# integrated_adc.net
KiCad netlist of a schematic drawn in EAGLE
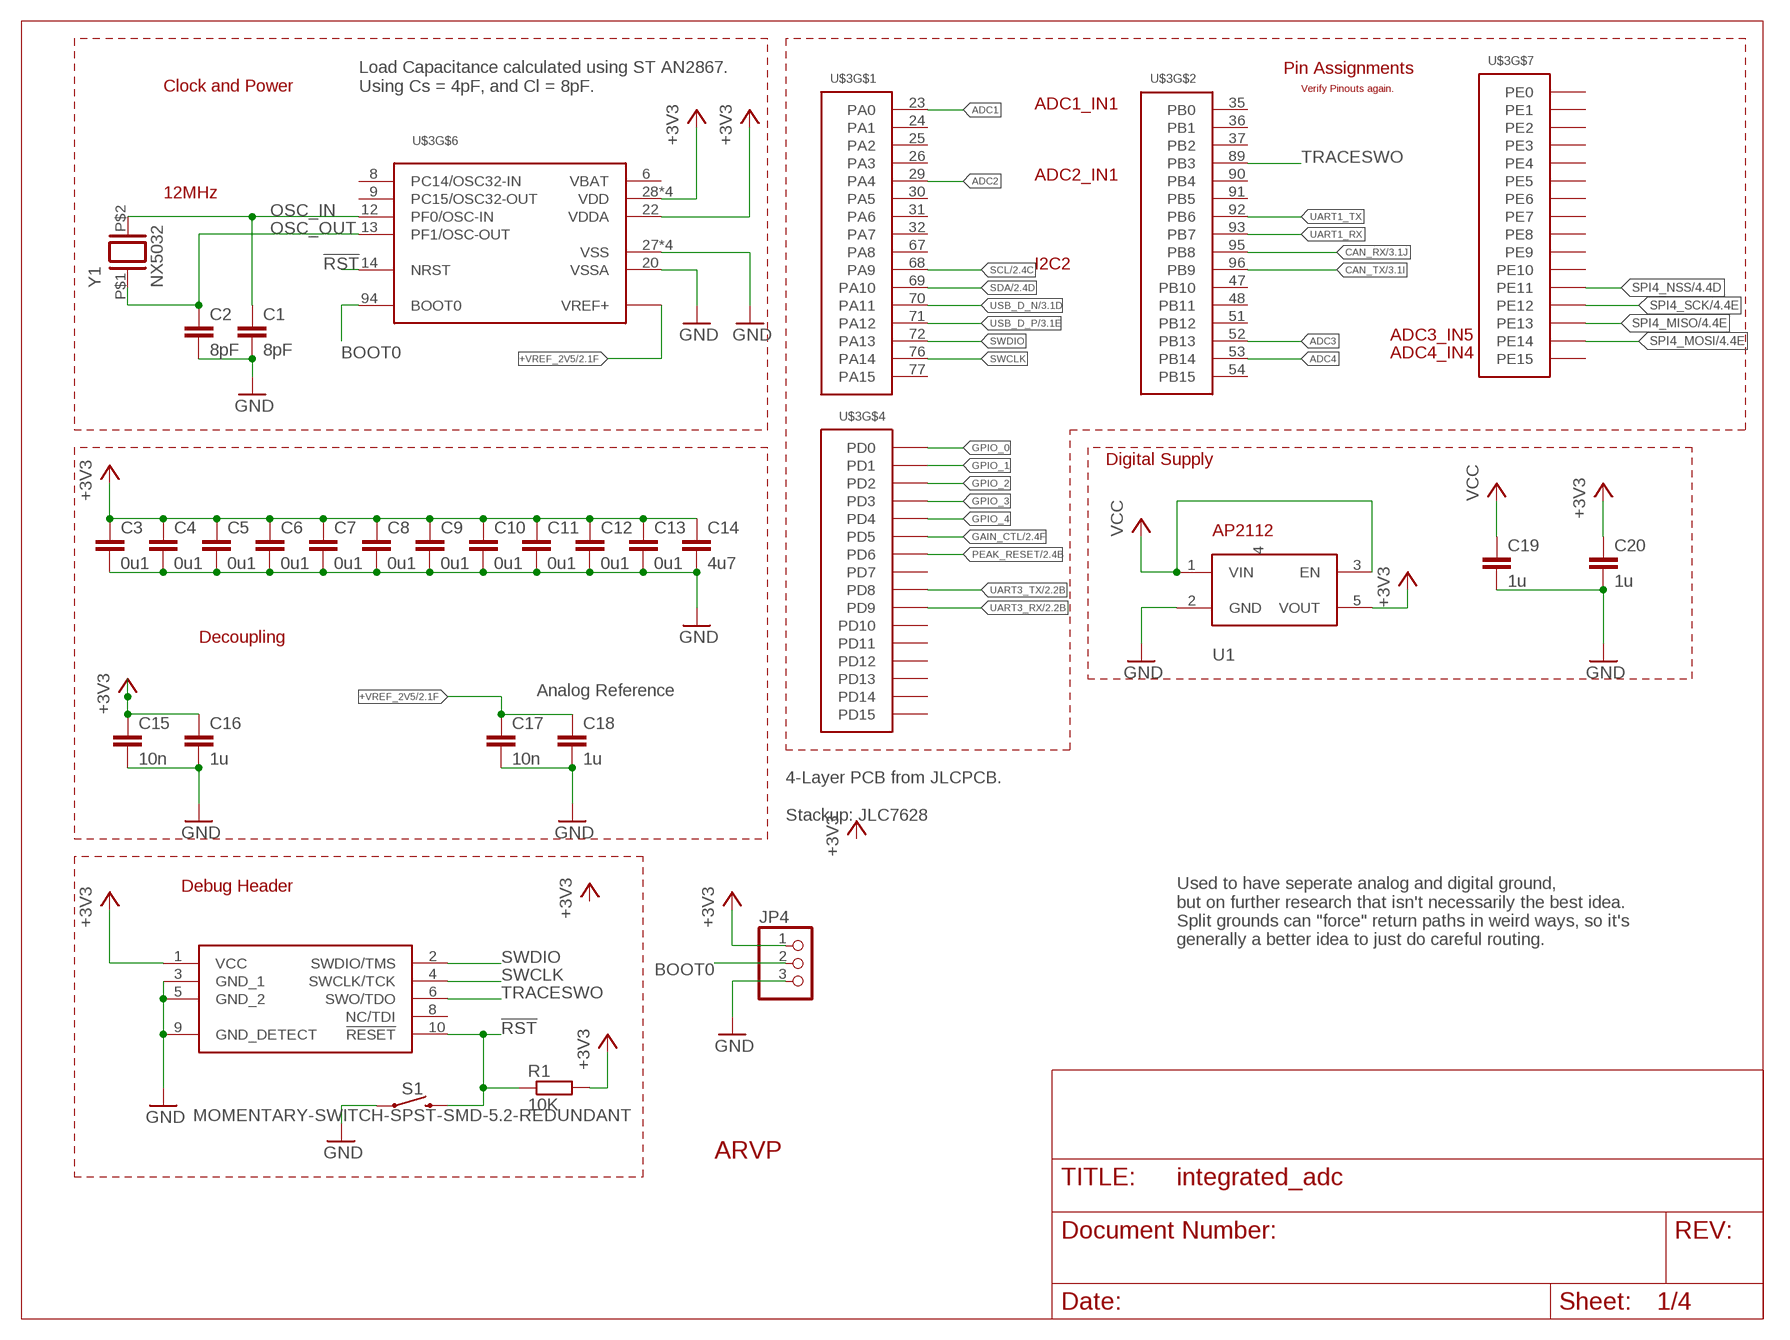
[diagram p0: schematic, sheet 1]
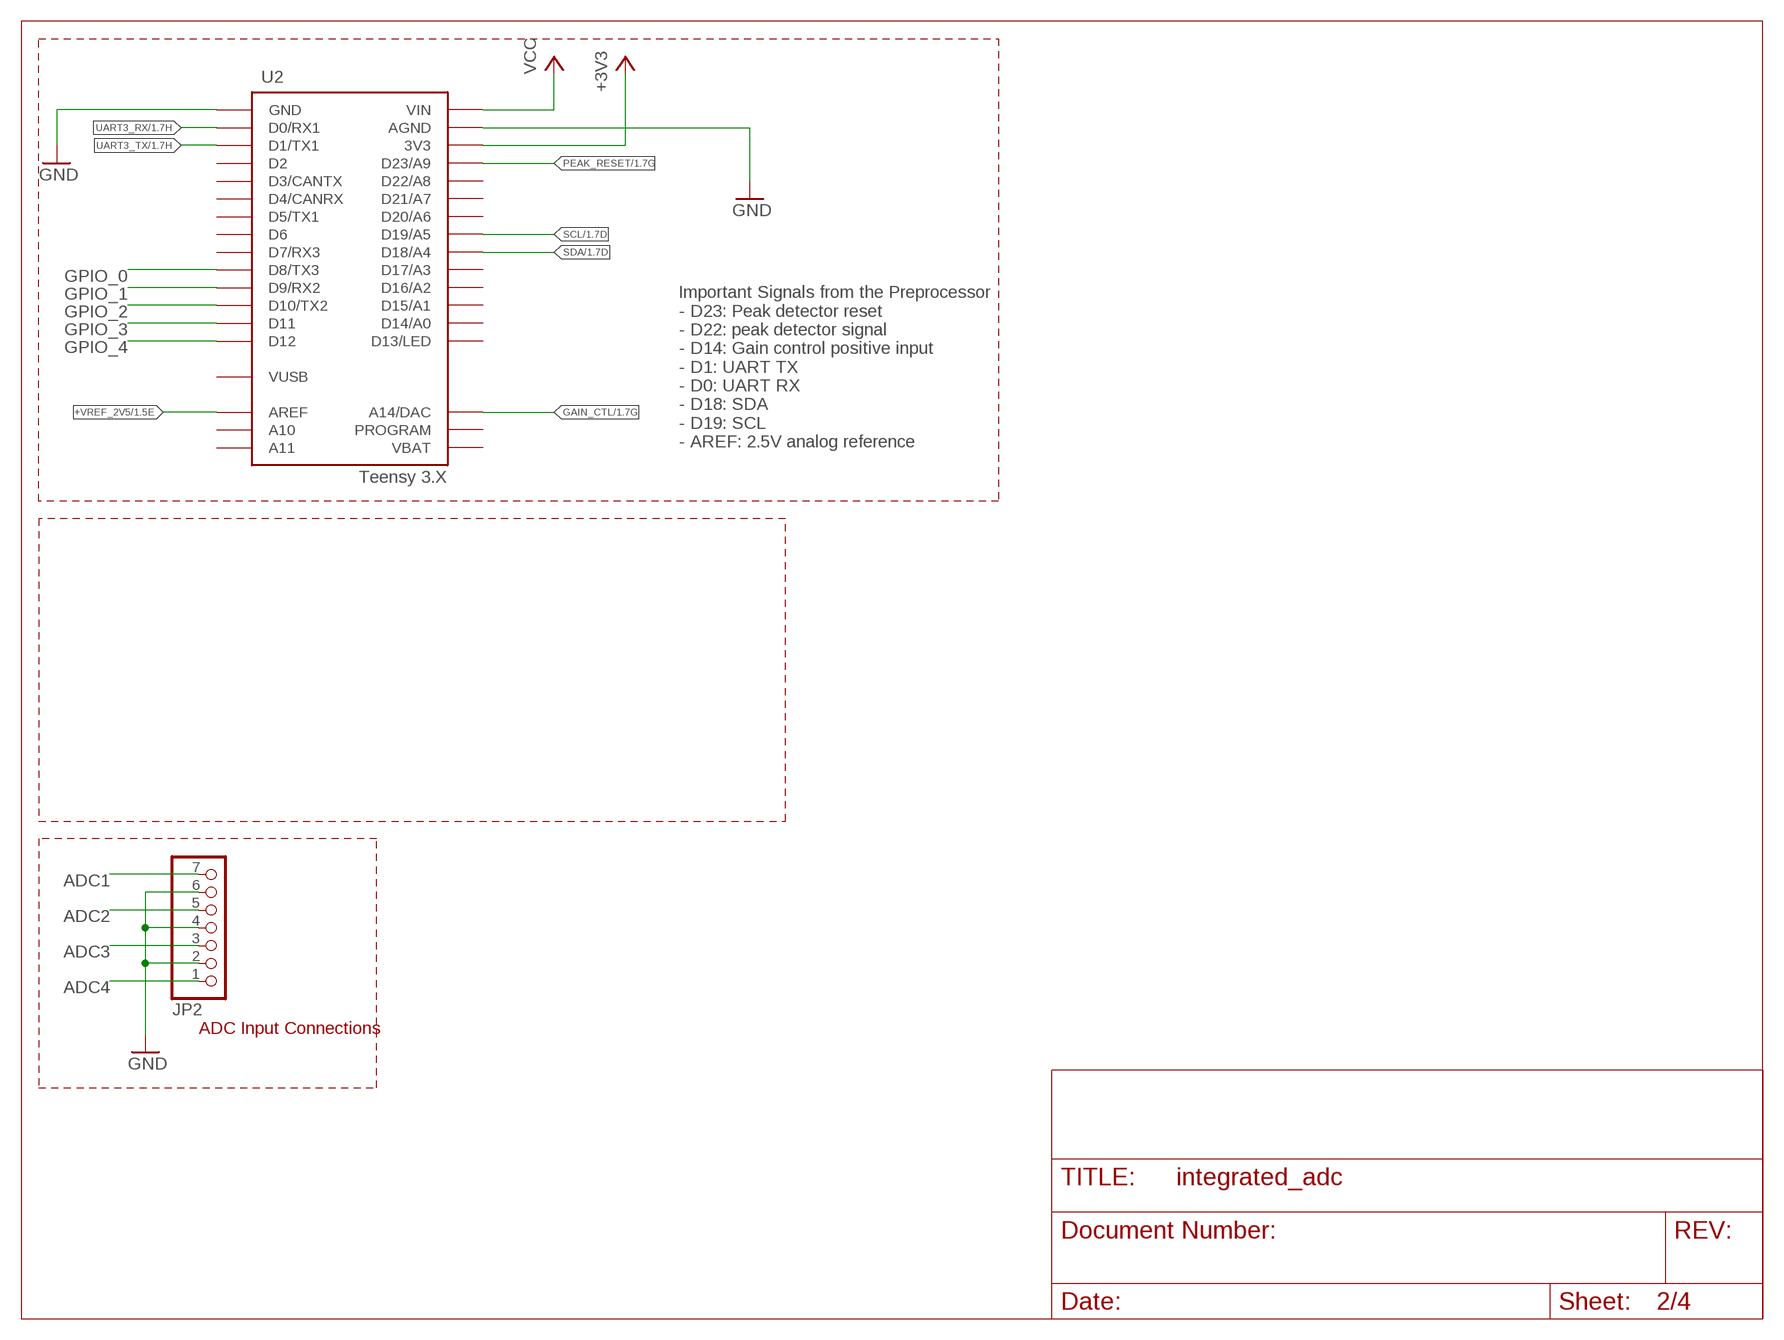
[diagram p1: schematic, sheet 2]
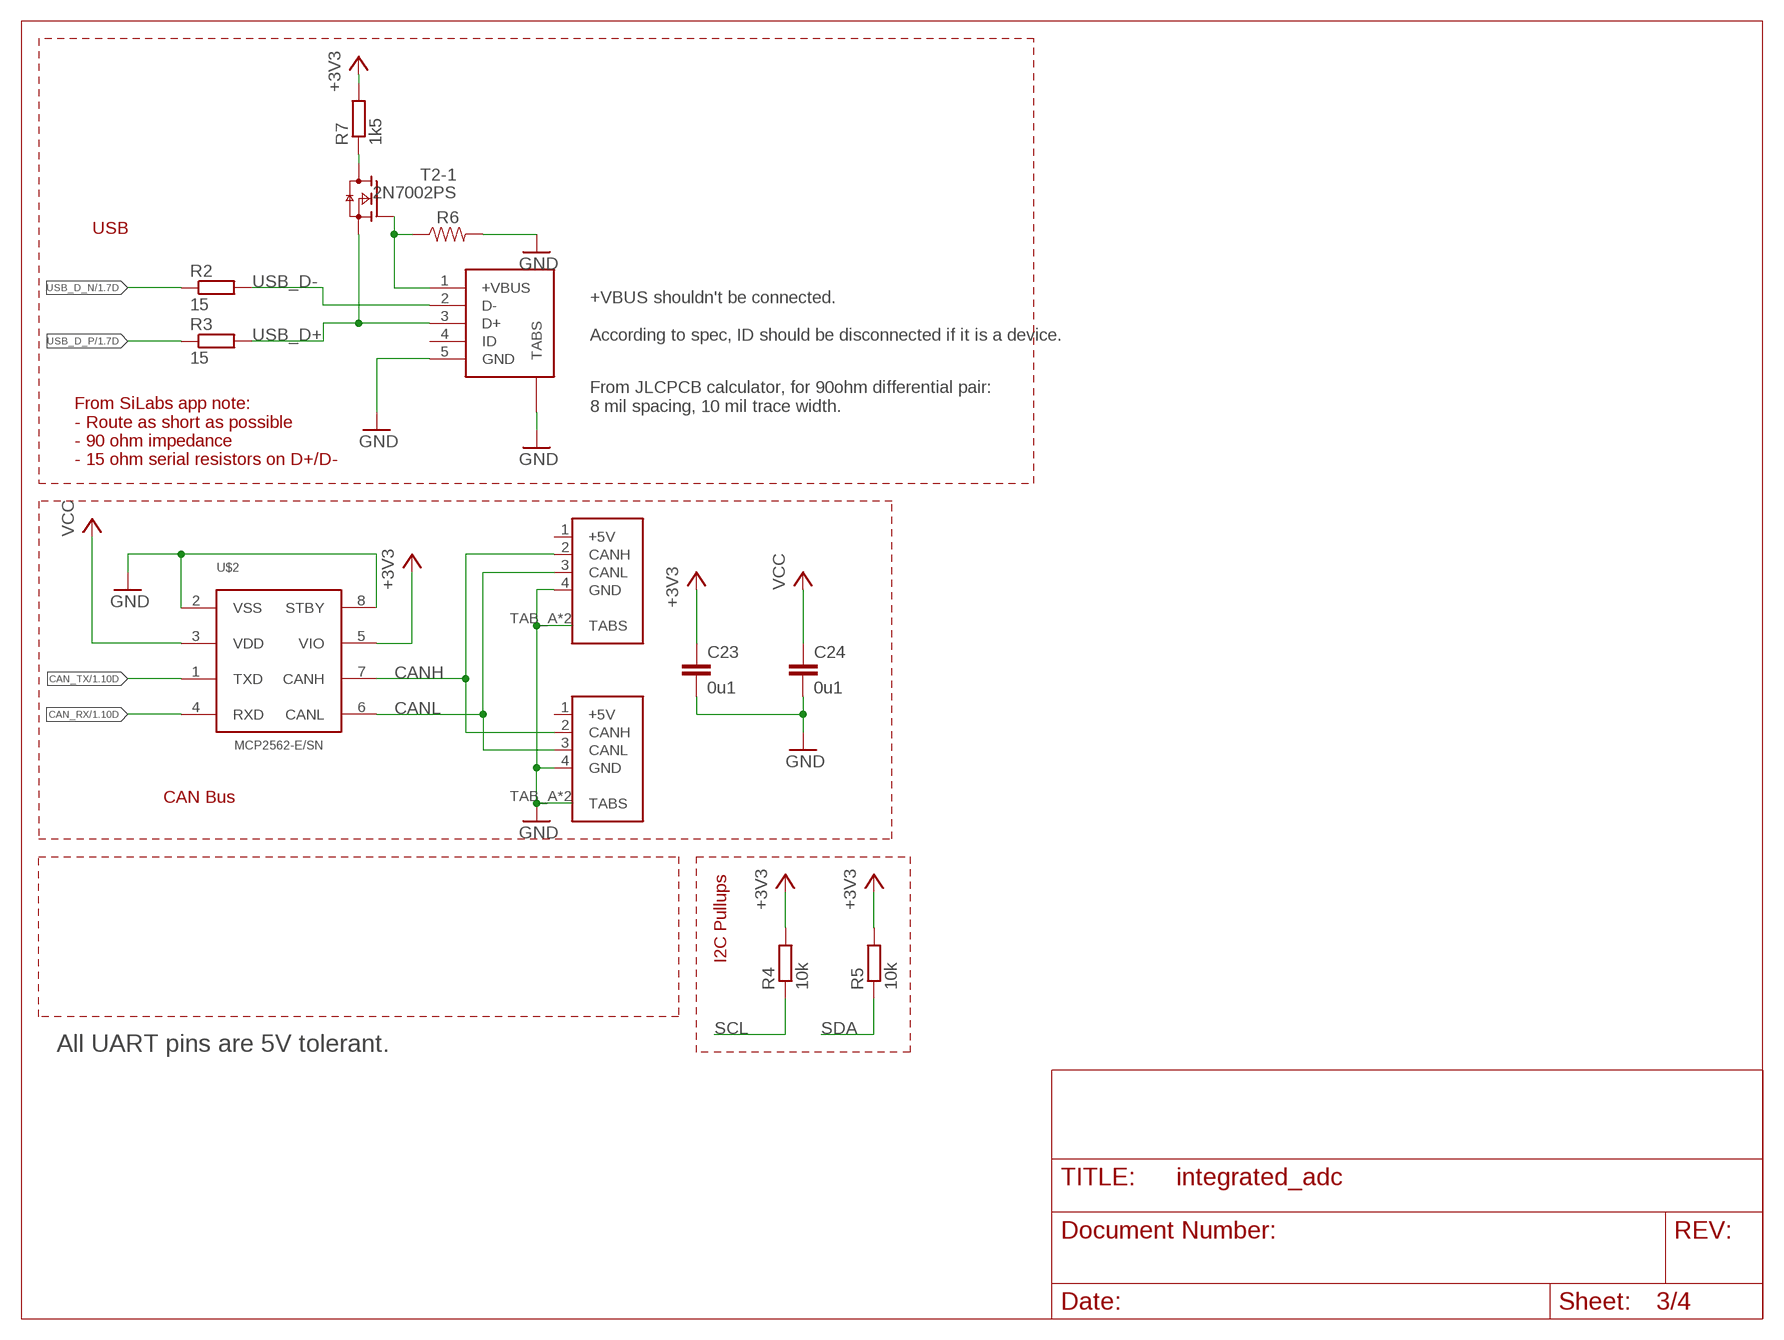
[diagram p2: schematic, sheet 3]
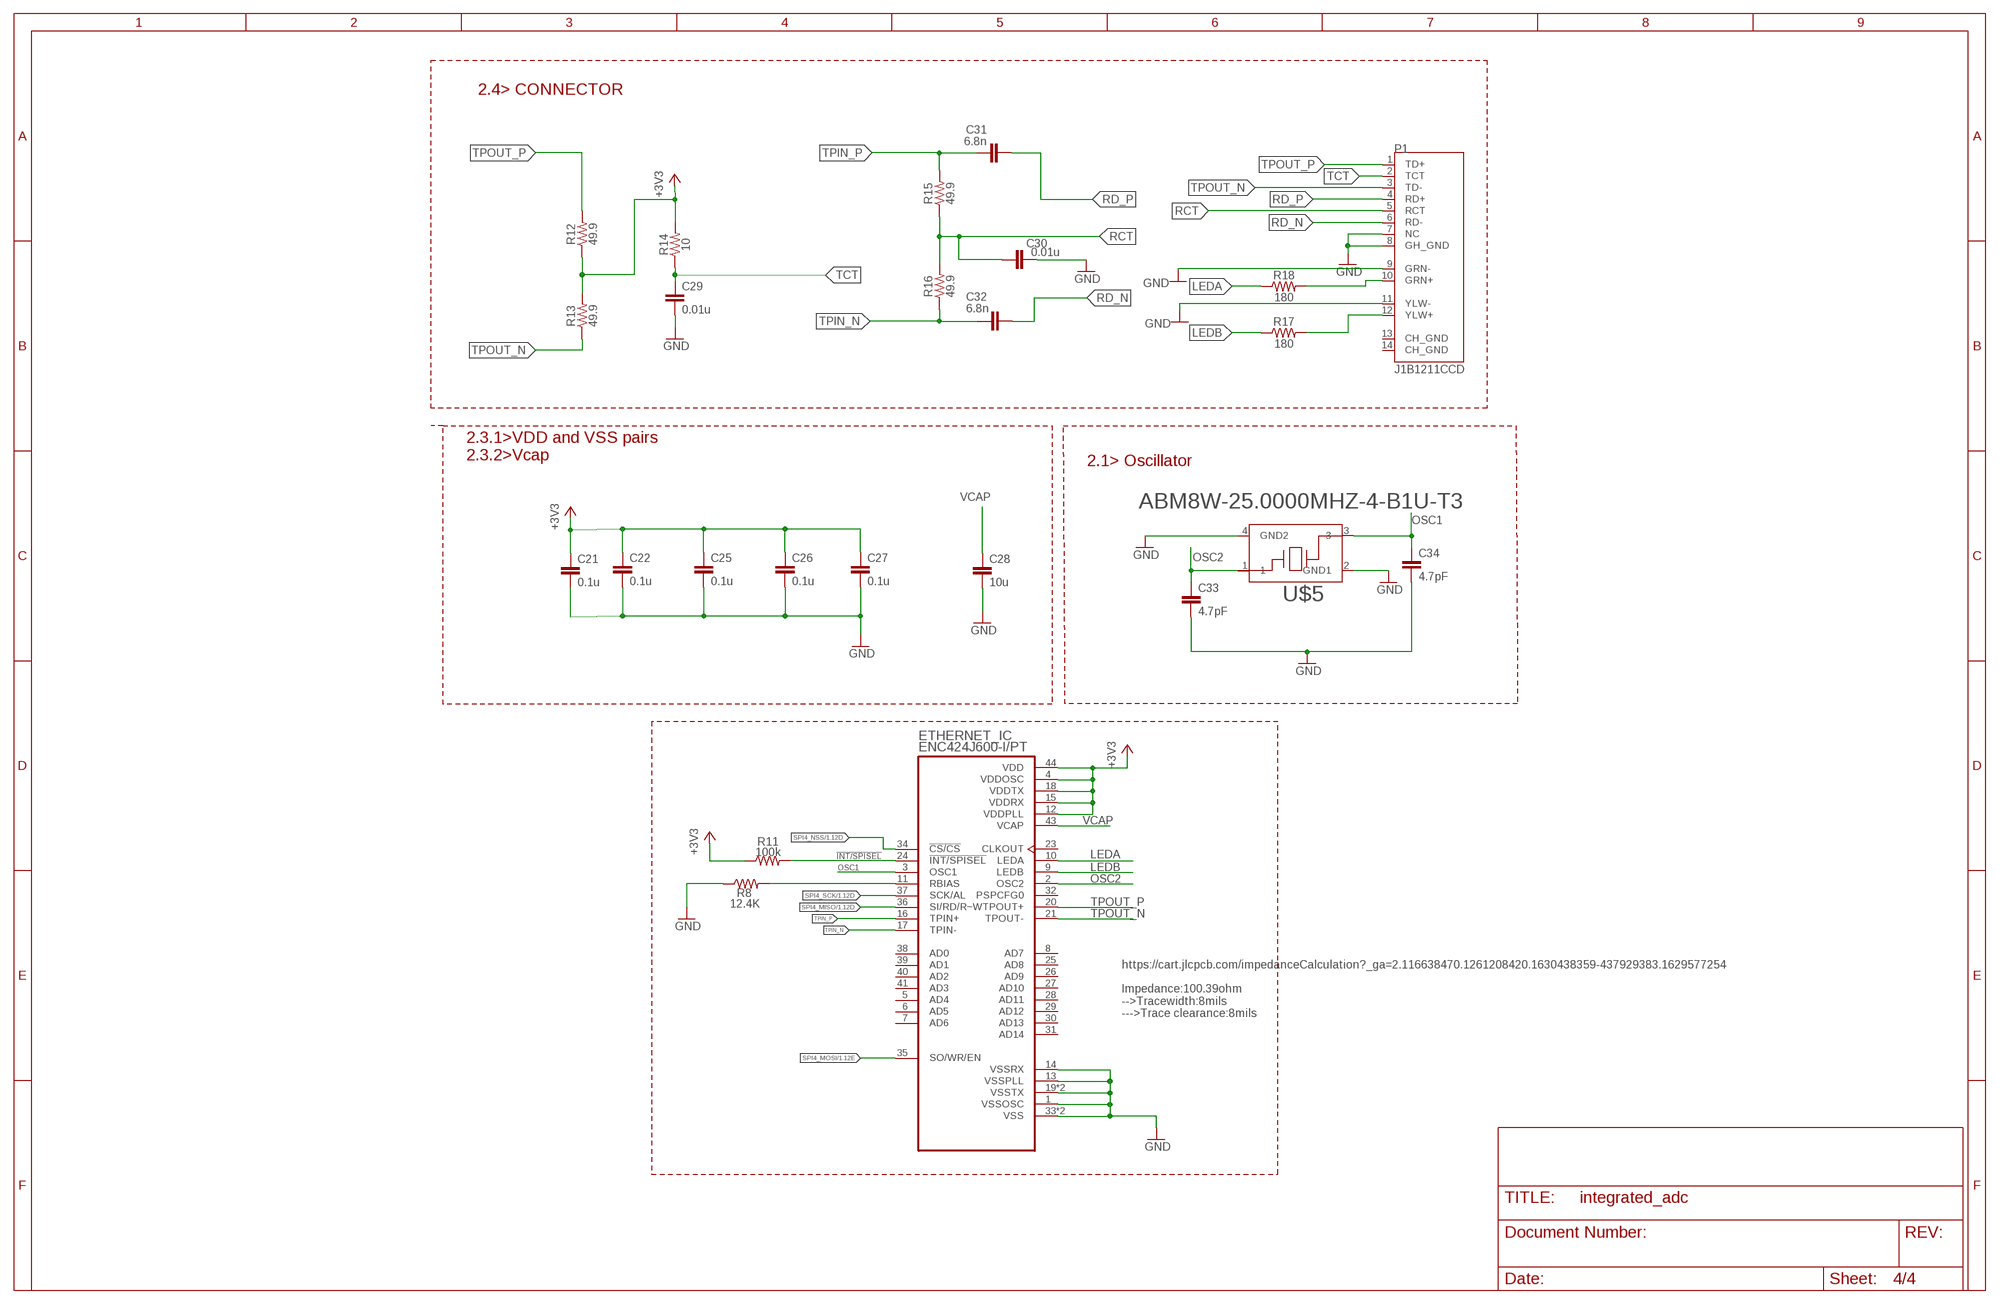
[diagram p3: schematic, sheet 4]

(export (version "E")
  (design (tool "Eeschema 10.0.6"))
  (components
    (comp (ref "ARVP1")
      (value "ARVP_LOGO")
      (footprint "eagle-import:ARVP")
      (libsource (lib "eagle-import") (part "ARVP_LOGO"))
    )
    (comp (ref "C1")
      (value "8pF")
      (footprint "eagle-import:C0805")
      (libsource (lib "eagle-import") (part "resistor_348_C-EUC0805"))
    )
    (comp (ref "C2")
      (value "8pF")
      (footprint "eagle-import:C0805")
      (libsource (lib "eagle-import") (part "resistor_348_C-EUC0805"))
    )
    (comp (ref "C3")
      (value "0u1")
      (footprint "eagle-import:C0805")
      (libsource (lib "eagle-import") (part "resistor_348_C-EUC0805"))
    )
    (comp (ref "C4")
      (value "0u1")
      (footprint "eagle-import:C0805")
      (libsource (lib "eagle-import") (part "resistor_348_C-EUC0805"))
    )
    (comp (ref "C5")
      (value "0u1")
      (footprint "eagle-import:C0805")
      (libsource (lib "eagle-import") (part "resistor_348_C-EUC0805"))
    )
    (comp (ref "C6")
      (value "0u1")
      (footprint "eagle-import:C0805")
      (libsource (lib "eagle-import") (part "resistor_348_C-EUC0805"))
    )
    (comp (ref "C7")
      (value "0u1")
      (footprint "eagle-import:C0805")
      (libsource (lib "eagle-import") (part "resistor_348_C-EUC0805"))
    )
    (comp (ref "C8")
      (value "0u1")
      (footprint "eagle-import:C0805")
      (libsource (lib "eagle-import") (part "resistor_348_C-EUC0805"))
    )
    (comp (ref "C9")
      (value "0u1")
      (footprint "eagle-import:C0805")
      (libsource (lib "eagle-import") (part "resistor_348_C-EUC0805"))
    )
    (comp (ref "C10")
      (value "0u1")
      (footprint "eagle-import:C0805")
      (libsource (lib "eagle-import") (part "resistor_348_C-EUC0805"))
    )
    (comp (ref "C11")
      (value "0u1")
      (footprint "eagle-import:C0805")
      (libsource (lib "eagle-import") (part "resistor_348_C-EUC0805"))
    )
    (comp (ref "C12")
      (value "0u1")
      (footprint "eagle-import:C0805")
      (libsource (lib "eagle-import") (part "resistor_348_C-EUC0805"))
    )
    (comp (ref "C13")
      (value "0u1")
      (footprint "eagle-import:C0805")
      (libsource (lib "eagle-import") (part "resistor_348_C-EUC0805"))
    )
    (comp (ref "C14")
      (value "4u7")
      (footprint "eagle-import:C0805")
      (libsource (lib "eagle-import") (part "resistor_348_C-EUC0805"))
    )
    (comp (ref "C15")
      (value "10n")
      (footprint "eagle-import:C0805")
      (libsource (lib "eagle-import") (part "resistor_348_C-EUC0805"))
    )
    (comp (ref "C16")
      (value "1u")
      (footprint "eagle-import:C0805")
      (libsource (lib "eagle-import") (part "resistor_348_C-EUC0805"))
    )
    (comp (ref "C17")
      (value "10n")
      (footprint "eagle-import:C0805")
      (libsource (lib "eagle-import") (part "resistor_348_C-EUC0805"))
    )
    (comp (ref "C18")
      (value "1u")
      (footprint "eagle-import:C0805")
      (libsource (lib "eagle-import") (part "resistor_348_C-EUC0805"))
    )
    (comp (ref "C19")
      (value "1u")
      (footprint "eagle-import:C0805")
      (libsource (lib "eagle-import") (part "resistor_348_C-EUC0805"))
    )
    (comp (ref "C20")
      (value "1u")
      (footprint "eagle-import:C0805")
      (libsource (lib "eagle-import") (part "resistor_348_C-EUC0805"))
    )
    (comp (ref "JP1")
      (value "CORTEX-M-DBG")
      (footprint "eagle-import:FTSH-105-01-F-DV-007")
      (libsource (lib "eagle-import") (part "CORTEX-M-DBG"))
    )
    (comp (ref "JP4")
      (value "PINHD-1X3")
      (footprint "eagle-import:1X03")
      (libsource (lib "eagle-import") (part "PINHD-1X3"))
    )
    (comp (ref "R1")
      (value "10K")
      (footprint "eagle-import:R0805")
      (libsource (lib "eagle-import") (part "R-EU_R0805"))
    )
    (comp (ref "S1")
      (value "MOMENTARY-SWITCH-SPST-SMD-5.2-REDUNDANT")
      (footprint "eagle-import:TACTILE_SWITCH_SMD_5.2MM")
      (libsource (lib "eagle-import") (part "MOMENTARY-SWITCH-SPST-SMD-5.2-REDUNDANT"))
    )
    (comp (ref "U$3")
      (value "STM32F303VE")
      (footprint "eagle-import:LQFP100")
      (libsource (lib "eagle-import") (part "STM32F303VE"))
    )
    (comp (ref "U1")
      (value "AP2112K-3.3TRG1")
      (footprint "eagle-import:SOT25")
      (libsource (lib "eagle-import") (part "AP2112K-3.3TRG1"))
    )
    (comp (ref "Y1")
      (value "NX5032")
      (footprint "eagle-import:NX5032")
      (libsource (lib "eagle-import") (part "NX5032"))
    )
    (comp (ref "C23")
      (value "0u1")
      (footprint "eagle-import:C0805")
      (libsource (lib "eagle-import") (part "resistor_348_C-EUC0805"))
    )
    (comp (ref "C24")
      (value "0u1")
      (footprint "eagle-import:C0805")
      (libsource (lib "eagle-import") (part "resistor_348_C-EUC0805"))
    )
    (comp (ref "CON1")
      (value "UAVCAN_MICRO")
      (footprint "eagle-import:SM04B-GHS-TB")
      (libsource (lib "eagle-import") (part "UAVCAN_MICRO"))
    )
    (comp (ref "CON2")
      (value "UAVCAN_MICRO")
      (footprint "eagle-import:SM04B-GHS-TB")
      (libsource (lib "eagle-import") (part "UAVCAN_MICRO"))
    )
    (comp (ref "R2")
      (value "15")
      (footprint "eagle-import:R0805")
      (libsource (lib "eagle-import") (part "R-EU_R0805"))
    )
    (comp (ref "R3")
      (value "15")
      (footprint "eagle-import:R0805")
      (libsource (lib "eagle-import") (part "R-EU_R0805"))
    )
    (comp (ref "R4")
      (value "10k")
      (footprint "eagle-import:R0805")
      (libsource (lib "eagle-import") (part "R-EU_R0805"))
    )
    (comp (ref "R5")
      (value "10k")
      (footprint "eagle-import:R0805")
      (libsource (lib "eagle-import") (part "R-EU_R0805"))
    )
    (comp (ref "R6")
      (value "RESISTOR1206")
      (footprint "eagle-import:1206")
      (libsource (lib "eagle-import") (part "RESISTOR1206"))
    )
    (comp (ref "R7")
      (value "1k5")
      (footprint "eagle-import:R0805")
      (libsource (lib "eagle-import") (part "R-EU_R0805"))
    )
    (comp (ref "T2")
      (value "2N7002PS")
      (footprint "eagle-import:SOT363")
      (libsource (lib "eagle-import") (part "2N7002PS"))
    )
    (comp (ref "U$2")
      (value "MCP2562-E/SN")
      (footprint "eagle-import:SOIC8")
      (libsource (lib "eagle-import") (part "MCP2562-E/SN"))
    )
    (comp (ref "U$4")
      (value "AMPHENOL_MICROB-USB")
      (footprint "eagle-import:AMPHENOL_MICROB_SMD")
      (libsource (lib "eagle-import") (part "AMPHENOL_MICROB-USB"))
    )
    (comp (ref "C21")
      (value "0.1u")
      (footprint "eagle-import:C0402")
      (libsource (lib "eagle-import") (part "C-EUC0402"))
    )
    (comp (ref "C22")
      (value "0.1u")
      (footprint "eagle-import:C0402")
      (libsource (lib "eagle-import") (part "C-EUC0402"))
    )
    (comp (ref "C25")
      (value "0.1u")
      (footprint "eagle-import:C0402")
      (libsource (lib "eagle-import") (part "C-EUC0402"))
    )
    (comp (ref "C26")
      (value "0.1u")
      (footprint "eagle-import:C0402")
      (libsource (lib "eagle-import") (part "C-EUC0402"))
    )
    (comp (ref "C27")
      (value "0.1u")
      (footprint "eagle-import:C0402")
      (libsource (lib "eagle-import") (part "C-EUC0402"))
    )
    (comp (ref "C28")
      (value "10u")
      (footprint "eagle-import:C0402")
      (libsource (lib "eagle-import") (part "C-EUC0402"))
    )
    (comp (ref "C29")
      (value "0.01u")
      (footprint "eagle-import:C0402")
      (libsource (lib "eagle-import") (part "C-EUC0402"))
    )
    (comp (ref "C30")
      (value "0.01u")
      (footprint "eagle-import:C0402")
      (libsource (lib "eagle-import") (part "C-EUC0402"))
    )
    (comp (ref "C31")
      (value "6.8n")
      (footprint "eagle-import:C0402")
      (libsource (lib "eagle-import") (part "C-EUC0402"))
    )
    (comp (ref "C32")
      (value "6.8n")
      (footprint "eagle-import:C0402")
      (libsource (lib "eagle-import") (part "C-EUC0402"))
    )
    (comp (ref "C33")
      (value "4.7pF")
      (footprint "eagle-import:C0402")
      (libsource (lib "eagle-import") (part "rcl_334_C-EUC0402"))
    )
    (comp (ref "C34")
      (value "4.7pF")
      (footprint "eagle-import:C0402")
      (libsource (lib "eagle-import") (part "rcl_334_C-EUC0402"))
    )
    (comp (ref "ETHERNET_IC")
      (value "ENC424J600-I/PT")
      (footprint "eagle-import:QFP80P1200X1200X120-44N")
      (fields (field (name "MF") "Microchip"))
      (libsource (lib "eagle-import") (part "ENC424J600-I/PT"))
    )
    (comp (ref "P1")
      (value "J1B1211CCD")
      (footprint "eagle-import:J1B1211CCD")
      (fields (field (name "MF") "Ceetus"))
      (libsource (lib "eagle-import") (part "J1B1211CCD"))
    )
    (comp (ref "R8")
      (value "12.4K")
      (footprint "eagle-import:0603")
      (libsource (lib "eagle-import") (part "1.8MOHM"))
    )
    (comp (ref "R11")
      (value "100k")
      (footprint "eagle-import:0603")
      (libsource (lib "eagle-import") (part "100KOHM-0603-1/10W-1%"))
    )
    (comp (ref "R12")
      (value "49.9")
      (footprint "eagle-import:0603")
      (libsource (lib "eagle-import") (part "715OHM-0603-1/10W-1%"))
    )
    (comp (ref "R13")
      (value "49.9")
      (footprint "eagle-import:0603")
      (libsource (lib "eagle-import") (part "715OHM-0603-1/10W-1%"))
    )
    (comp (ref "R14")
      (value "10")
      (footprint "eagle-import:0603")
      (libsource (lib "eagle-import") (part "715OHM-0603-1/10W-1%"))
    )
    (comp (ref "R15")
      (value "49.9")
      (footprint "eagle-import:0603")
      (libsource (lib "eagle-import") (part "715OHM-0603-1/10W-1%"))
    )
    (comp (ref "R16")
      (value "49.9")
      (footprint "eagle-import:0603")
      (libsource (lib "eagle-import") (part "715OHM-0603-1/10W-1%"))
    )
    (comp (ref "R17")
      (value "180")
      (footprint "eagle-import:RESC1608X55N")
      (fields
        (field (name "DIGI-KEY_PART_NUMBER") "13-AC0603FR-0712K4LCT-ND")
        (field (name "MF") "Yageo")
        (field (name "MP") "AC0603FR-0712K4L")
      )
      (libsource (lib "eagle-import") (part "AC0603FR-0712K4L"))
    )
    (comp (ref "R18")
      (value "180")
      (footprint "eagle-import:RESC1608X55N")
      (fields
        (field (name "DIGI-KEY_PART_NUMBER") "13-AC0603FR-0712K4LCT-ND")
        (field (name "MF") "Yageo")
        (field (name "MP") "AC0603FR-0712K4L")
      )
      (libsource (lib "eagle-import") (part "AC0603FR-0712K4L"))
    )
    (comp (ref "U$5")
      (value "ABM8W-25.0000MHZ-4-B1U-T3")
      (footprint "eagle-import:XTAL_ABM8W-25.0000MHZ-4-B1U-T3")
      (libsource (lib "eagle-import") (part "ABM8W-25.0000MHZ-4-B1U-T3"))
    )
    (comp (ref "JP2")
      (value "PINHD-1X7/90")
      (footprint "eagle-import:1X07_90")
      (libsource (lib "eagle-import") (part "PINHD-1X7/90"))
    )
    (comp (ref "U2")
      (value "TEENSY_3.X_PINOUT")
      (footprint "eagle-import:TEENSY_3.X_PINOUT")
      (libsource (lib "eagle-import") (part "TEENSY_3.X_PINOUT"))
    )
  )
  (nets
    (net (code "1") (name "+3V3") (class "Default")
      (node (ref "C10") (pin "1") (pinfunction "1_1") (pintype "passive"))
      (node (ref "C11") (pin "1") (pinfunction "1_1") (pintype "passive"))
      (node (ref "C12") (pin "1") (pinfunction "1_1") (pintype "passive"))
      (node (ref "C13") (pin "1") (pinfunction "1_1") (pintype "passive"))
      (node (ref "C14") (pin "1") (pinfunction "1_1") (pintype "passive"))
      (node (ref "C15") (pin "1") (pinfunction "1_1") (pintype "passive"))
      (node (ref "C16") (pin "1") (pinfunction "1_1") (pintype "passive"))
      (node (ref "C20") (pin "1") (pinfunction "1_1") (pintype "passive"))
      (node (ref "C21") (pin "1") (pinfunction "1_1") (pintype "passive"))
      (node (ref "C22") (pin "1") (pinfunction "1_1") (pintype "passive"))
      (node (ref "C23") (pin "1") (pinfunction "1_1") (pintype "passive"))
      (node (ref "C25") (pin "1") (pinfunction "1_1") (pintype "passive"))
      (node (ref "C26") (pin "1") (pinfunction "1_1") (pintype "passive"))
      (node (ref "C27") (pin "1") (pinfunction "1_1") (pintype "passive"))
      (node (ref "C3") (pin "1") (pinfunction "1_1") (pintype "passive"))
      (node (ref "C4") (pin "1") (pinfunction "1_1") (pintype "passive"))
      (node (ref "C5") (pin "1") (pinfunction "1_1") (pintype "passive"))
      (node (ref "C6") (pin "1") (pinfunction "1_1") (pintype "passive"))
      (node (ref "C7") (pin "1") (pinfunction "1_1") (pintype "passive"))
      (node (ref "C8") (pin "1") (pinfunction "1_1") (pintype "passive"))
      (node (ref "C9") (pin "1") (pinfunction "1_1") (pintype "passive"))
      (node (ref "ETHERNET_IC") (pin "12") (pinfunction "VDDPLL_12") (pintype "power_in"))
      (node (ref "ETHERNET_IC") (pin "15") (pinfunction "VDDRX_15") (pintype "power_in"))
      (node (ref "ETHERNET_IC") (pin "18") (pinfunction "VDDTX_18") (pintype "power_in"))
      (node (ref "ETHERNET_IC") (pin "4") (pinfunction "VDDOSC_4") (pintype "power_in"))
      (node (ref "ETHERNET_IC") (pin "44") (pinfunction "VDD_44") (pintype "power_in"))
      (node (ref "JP1") (pin "1") (pinfunction "VCC_1") (pintype "bidirectional"))
      (node (ref "JP4") (pin "1") (pinfunction "1_1") (pintype "passive"))
      (node (ref "R1") (pin "2") (pinfunction "2_2") (pintype "passive"))
      (node (ref "R11") (pin "1") (pinfunction "1_1") (pintype "passive"))
      (node (ref "R12") (pin "1") (pinfunction "1_1") (pintype "passive"))
      (node (ref "R13") (pin "2") (pinfunction "2_2") (pintype "passive"))
      (node (ref "R14") (pin "2") (pinfunction "2_2") (pintype "passive"))
      (node (ref "R4") (pin "2") (pinfunction "2_2") (pintype "passive"))
      (node (ref "R5") (pin "2") (pinfunction "2_2") (pintype "passive"))
      (node (ref "R7") (pin "2") (pinfunction "2_2") (pintype "passive"))
      (node (ref "U$2") (pin "5") (pinfunction "VIO_5") (pintype "bidirectional"))
      (node (ref "U$3") (pin "100") (pinfunction "VDD_100") (pintype "bidirectional"))
      (node (ref "U$3") (pin "22") (pinfunction "VDDA_22") (pintype "bidirectional"))
      (node (ref "U$3") (pin "28") (pinfunction "VDD_28") (pintype "bidirectional"))
      (node (ref "U$3") (pin "50") (pinfunction "VDD_50") (pintype "bidirectional"))
      (node (ref "U$3") (pin "75") (pinfunction "VDD_75") (pintype "bidirectional"))
      (node (ref "U1") (pin "5") (pinfunction "VOUT_5") (pintype "bidirectional"))
      (node (ref "U2") (pin "3V3") (pinfunction "3V3_3V3") (pintype "power_in"))
      (node (ref "U2") (pin "3V3_2") (pinfunction "3V3_3V3_2") (pintype "power_in"))
    )
    (net (code "2") (name "+VREF_2V5") (class "Default")
      (node (ref "C17") (pin "1") (pinfunction "1_1") (pintype "passive"))
      (node (ref "C18") (pin "1") (pinfunction "1_1") (pintype "passive"))
      (node (ref "U$3") (pin "21") (pinfunction "VREF+_21") (pintype "input"))
      (node (ref "U2") (pin "AREF") (pinfunction "AREF_AREF") (pintype "input"))
    )
    (net (code "3") (name "ADC1") (class "Default")
      (node (ref "JP2") (pin "7") (pinfunction "7_7") (pintype "passive"))
      (node (ref "U$3") (pin "23") (pinfunction "PA0_23") (pintype "bidirectional"))
    )
    (net (code "4") (name "ADC2") (class "Default")
      (node (ref "JP2") (pin "5") (pinfunction "5_5") (pintype "passive"))
      (node (ref "U$3") (pin "29") (pinfunction "PA4_29") (pintype "bidirectional"))
    )
    (net (code "5") (name "ADC3") (class "Default")
      (node (ref "JP2") (pin "3") (pinfunction "3_3") (pintype "passive"))
      (node (ref "U$3") (pin "52") (pinfunction "PB13_52") (pintype "bidirectional"))
    )
    (net (code "6") (name "ADC4") (class "Default")
      (node (ref "JP2") (pin "1") (pinfunction "1_1") (pintype "passive"))
      (node (ref "U$3") (pin "53") (pinfunction "PB14_53") (pintype "bidirectional"))
    )
    (net (code "7") (name "BOOT0") (class "Default")
      (node (ref "JP4") (pin "2") (pinfunction "2_2") (pintype "passive"))
      (node (ref "U$3") (pin "94") (pinfunction "BOOT0_94") (pintype "bidirectional"))
    )
    (net (code "8") (name "CANH") (class "Default")
      (node (ref "CON1") (pin "2") (pinfunction "CANH_2") (pintype "bidirectional"))
      (node (ref "CON2") (pin "2") (pinfunction "CANH_2") (pintype "bidirectional"))
      (node (ref "U$2") (pin "7") (pinfunction "CANH_7") (pintype "bidirectional"))
    )
    (net (code "9") (name "CANL") (class "Default")
      (node (ref "CON1") (pin "3") (pinfunction "CANL_3") (pintype "bidirectional"))
      (node (ref "CON2") (pin "3") (pinfunction "CANL_3") (pintype "bidirectional"))
      (node (ref "U$2") (pin "6") (pinfunction "CANL_6") (pintype "bidirectional"))
    )
    (net (code "10") (name "CAN_RX") (class "Default")
      (node (ref "U$2") (pin "4") (pinfunction "RXD_4") (pintype "bidirectional"))
      (node (ref "U$3") (pin "95") (pinfunction "PB8_95") (pintype "bidirectional"))
    )
    (net (code "11") (name "CAN_TX") (class "Default")
      (node (ref "U$2") (pin "1") (pinfunction "TXD_1") (pintype "bidirectional"))
      (node (ref "U$3") (pin "96") (pinfunction "PB9_96") (pintype "bidirectional"))
    )
    (net (code "12") (name "GAIN_CTL") (class "Default")
      (node (ref "U$3") (pin "86") (pinfunction "PD5_86") (pintype "input"))
      (node (ref "U2") (pin "A14") (pinfunction "A14/DAC_A14") (pintype "bidirectional"))
    )
    (net (code "13") (name "GND") (class "Default")
      (node (ref "C1") (pin "2") (pinfunction "2_2") (pintype "passive"))
      (node (ref "C10") (pin "2") (pinfunction "2_2") (pintype "passive"))
      (node (ref "C11") (pin "2") (pinfunction "2_2") (pintype "passive"))
      (node (ref "C12") (pin "2") (pinfunction "2_2") (pintype "passive"))
      (node (ref "C13") (pin "2") (pinfunction "2_2") (pintype "passive"))
      (node (ref "C14") (pin "2") (pinfunction "2_2") (pintype "passive"))
      (node (ref "C15") (pin "2") (pinfunction "2_2") (pintype "passive"))
      (node (ref "C16") (pin "2") (pinfunction "2_2") (pintype "passive"))
      (node (ref "C17") (pin "2") (pinfunction "2_2") (pintype "passive"))
      (node (ref "C18") (pin "2") (pinfunction "2_2") (pintype "passive"))
      (node (ref "C19") (pin "2") (pinfunction "2_2") (pintype "passive"))
      (node (ref "C2") (pin "2") (pinfunction "2_2") (pintype "passive"))
      (node (ref "C20") (pin "2") (pinfunction "2_2") (pintype "passive"))
      (node (ref "C21") (pin "2") (pinfunction "2_2") (pintype "passive"))
      (node (ref "C22") (pin "2") (pinfunction "2_2") (pintype "passive"))
      (node (ref "C23") (pin "2") (pinfunction "2_2") (pintype "passive"))
      (node (ref "C24") (pin "2") (pinfunction "2_2") (pintype "passive"))
      (node (ref "C25") (pin "2") (pinfunction "2_2") (pintype "passive"))
      (node (ref "C26") (pin "2") (pinfunction "2_2") (pintype "passive"))
      (node (ref "C27") (pin "2") (pinfunction "2_2") (pintype "passive"))
      (node (ref "C28") (pin "2") (pinfunction "2_2") (pintype "passive"))
      (node (ref "C29") (pin "2") (pinfunction "2_2") (pintype "passive"))
      (node (ref "C3") (pin "2") (pinfunction "2_2") (pintype "passive"))
      (node (ref "C30") (pin "2") (pinfunction "2_2") (pintype "passive"))
      (node (ref "C33") (pin "2") (pinfunction "2_2") (pintype "passive"))
      (node (ref "C34") (pin "2") (pinfunction "2_2") (pintype "passive"))
      (node (ref "C4") (pin "2") (pinfunction "2_2") (pintype "passive"))
      (node (ref "C5") (pin "2") (pinfunction "2_2") (pintype "passive"))
      (node (ref "C6") (pin "2") (pinfunction "2_2") (pintype "passive"))
      (node (ref "C7") (pin "2") (pinfunction "2_2") (pintype "passive"))
      (node (ref "C8") (pin "2") (pinfunction "2_2") (pintype "passive"))
      (node (ref "C9") (pin "2") (pinfunction "2_2") (pintype "passive"))
      (node (ref "CON1") (pin "4") (pinfunction "GND_4") (pintype "bidirectional"))
      (node (ref "CON1") (pin "TAB_A") (pinfunction "TABS_TAB_A") (pintype "bidirectional"))
      (node (ref "CON1") (pin "TAB_B") (pinfunction "TABS_TAB_B") (pintype "bidirectional"))
      (node (ref "CON2") (pin "4") (pinfunction "GND_4") (pintype "bidirectional"))
      (node (ref "CON2") (pin "TAB_A") (pinfunction "TABS_TAB_A") (pintype "bidirectional"))
      (node (ref "CON2") (pin "TAB_B") (pinfunction "TABS_TAB_B") (pintype "bidirectional"))
      (node (ref "ETHERNET_IC") (pin "1") (pinfunction "VSSOSC_1") (pintype "power_in"))
      (node (ref "ETHERNET_IC") (pin "13") (pinfunction "VSSPLL_13") (pintype "power_in"))
      (node (ref "ETHERNET_IC") (pin "14") (pinfunction "VSSRX_14") (pintype "power_in"))
      (node (ref "ETHERNET_IC") (pin "19") (pinfunction "VSSTX_19") (pintype "power_in"))
      (node (ref "ETHERNET_IC") (pin "22") (pinfunction "VSSTX_22") (pintype "power_in"))
      (node (ref "ETHERNET_IC") (pin "33") (pinfunction "VSS_33") (pintype "power_in"))
      (node (ref "ETHERNET_IC") (pin "42") (pinfunction "VSS_42") (pintype "power_in"))
      (node (ref "JP1") (pin "3") (pinfunction "GND_1_3") (pintype "bidirectional"))
      (node (ref "JP1") (pin "5") (pinfunction "GND_2_5") (pintype "bidirectional"))
      (node (ref "JP1") (pin "9") (pinfunction "GND_DETECT_9") (pintype "bidirectional"))
      (node (ref "JP2") (pin "2") (pinfunction "2_2") (pintype "passive"))
      (node (ref "JP2") (pin "4") (pinfunction "4_4") (pintype "passive"))
      (node (ref "JP2") (pin "6") (pinfunction "6_6") (pintype "passive"))
      (node (ref "JP4") (pin "3") (pinfunction "3_3") (pintype "passive"))
      (node (ref "P1") (pin "11") (pinfunction "YLW-_11") (pintype "passive"))
      (node (ref "P1") (pin "7") (pinfunction "NC_7") (pintype "passive"))
      (node (ref "P1") (pin "8") (pinfunction "GH_GND_8") (pintype "passive"))
      (node (ref "P1") (pin "9") (pinfunction "GRN-_9") (pintype "passive"))
      (node (ref "R6") (pin "2") (pinfunction "2_2") (pintype "passive"))
      (node (ref "R8") (pin "1") (pinfunction "1_1") (pintype "passive"))
      (node (ref "S1") (pin "1") (pinfunction "1_1") (pintype "passive"))
      (node (ref "S1") (pin "2") (pinfunction "1_2") (pintype "passive"))
      (node (ref "U$2") (pin "2") (pinfunction "VSS_2") (pintype "bidirectional"))
      (node (ref "U$2") (pin "8") (pinfunction "STBY_8") (pintype "bidirectional"))
      (node (ref "U$3") (pin "20") (pinfunction "VSSA_20") (pintype "bidirectional"))
      (node (ref "U$3") (pin "27") (pinfunction "VSS_27") (pintype "bidirectional"))
      (node (ref "U$3") (pin "49") (pinfunction "VSS_49") (pintype "bidirectional"))
      (node (ref "U$3") (pin "74") (pinfunction "VSS_74") (pintype "bidirectional"))
      (node (ref "U$3") (pin "99") (pinfunction "VSS_99") (pintype "bidirectional"))
      (node (ref "U$4") (pin "5") (pinfunction "GND_5") (pintype "bidirectional"))
      (node (ref "U$4") (pin "TAB1") (pinfunction "TABS_TAB1") (pintype "bidirectional"))
      (node (ref "U$4") (pin "TAB2") (pinfunction "TABS_TAB2") (pintype "bidirectional"))
      (node (ref "U$4") (pin "TAB3") (pinfunction "TABS_TAB3") (pintype "bidirectional"))
      (node (ref "U$4") (pin "TAB4") (pinfunction "TABS_TAB4") (pintype "bidirectional"))
      (node (ref "U$5") (pin "2") (pinfunction "GND1_2") (pintype "bidirectional"))
      (node (ref "U$5") (pin "4") (pinfunction "GND2_4") (pintype "bidirectional"))
      (node (ref "U1") (pin "2") (pinfunction "GND_2") (pintype "bidirectional"))
      (node (ref "U2") (pin "AGND") (pinfunction "AGND_AGND") (pintype "power_in"))
      (node (ref "U2") (pin "GND_1") (pinfunction "GND_GND_1") (pintype "power_in"))
      (node (ref "U2") (pin "GND_2") (pinfunction "GND_GND_2") (pintype "power_in"))
    )
    (net (code "14") (name "GPIO_0") (class "Default")
      (node (ref "U$3") (pin "81") (pinfunction "PD0_81") (pintype "input"))
      (node (ref "U2") (pin "D8") (pinfunction "D8/TX3_D8") (pintype "bidirectional"))
    )
    (net (code "15") (name "GPIO_1") (class "Default")
      (node (ref "U$3") (pin "82") (pinfunction "PD1_82") (pintype "input"))
      (node (ref "U2") (pin "D9") (pinfunction "D9/RX2_D9") (pintype "bidirectional"))
    )
    (net (code "16") (name "GPIO_2") (class "Default")
      (node (ref "U$3") (pin "83") (pinfunction "PD2_83") (pintype "input"))
      (node (ref "U2") (pin "D10") (pinfunction "D10/TX2_D10") (pintype "bidirectional"))
    )
    (net (code "17") (name "GPIO_3") (class "Default")
      (node (ref "U$3") (pin "84") (pinfunction "PD3_84") (pintype "input"))
      (node (ref "U2") (pin "D11") (pinfunction "D11_D11") (pintype "bidirectional"))
    )
    (net (code "18") (name "GPIO_4") (class "Default")
      (node (ref "U$3") (pin "85") (pinfunction "PD4_85") (pintype "input"))
      (node (ref "U2") (pin "D12") (pinfunction "D12_D12") (pintype "bidirectional"))
    )
    (net (code "19") (name "LEDA") (class "Default")
      (node (ref "ETHERNET_IC") (pin "10") (pinfunction "LEDA_10") (pintype "output"))
      (node (ref "R18") (pin "1") (pinfunction "1_1") (pintype "passive"))
    )
    (net (code "20") (name "LEDB") (class "Default")
      (node (ref "ETHERNET_IC") (pin "9") (pinfunction "LEDB_9") (pintype "output"))
      (node (ref "R17") (pin "1") (pinfunction "1_1") (pintype "passive"))
    )
    (net (code "21") (name "Net-(ETHERNET_IC-RBIAS)") (class "Default")
      (node (ref "ETHERNET_IC") (pin "11") (pinfunction "RBIAS_11") (pintype "input"))
      (node (ref "R8") (pin "2") (pinfunction "2_2") (pintype "passive"))
    )
    (net (code "22") (name "Net-(P1-GRN+)") (class "Default")
      (node (ref "P1") (pin "10") (pinfunction "GRN+_10") (pintype "passive"))
      (node (ref "R18") (pin "2") (pinfunction "2_2") (pintype "passive"))
    )
    (net (code "23") (name "Net-(P1-YLW+)") (class "Default")
      (node (ref "P1") (pin "12") (pinfunction "YLW+_12") (pintype "passive"))
      (node (ref "R17") (pin "2") (pinfunction "2_2") (pintype "passive"))
    )
    (net (code "24") (name "Net-(T2A-D)") (class "Default")
      (node (ref "R7") (pin "1") (pinfunction "1_1") (pintype "passive"))
      (node (ref "T2") (pin "6") (pinfunction "D_6") (pintype "passive"))
    )
    (net (code "25") (name "Net-(T2A-G)") (class "Default")
      (node (ref "R6") (pin "1") (pinfunction "1_1") (pintype "passive"))
      (node (ref "T2") (pin "2") (pinfunction "G_2") (pintype "passive"))
      (node (ref "U$4") (pin "1") (pinfunction "+VBUS_1") (pintype "bidirectional"))
    )
    (net (code "26") (name "OSC1") (class "Default")
      (node (ref "C34") (pin "1") (pinfunction "1_1") (pintype "passive"))
      (node (ref "ETHERNET_IC") (pin "3") (pinfunction "OSC1_3") (pintype "input"))
      (node (ref "U$5") (pin "3") (pinfunction "3_3") (pintype "bidirectional"))
    )
    (net (code "27") (name "OSC2") (class "Default")
      (node (ref "C33") (pin "1") (pinfunction "1_1") (pintype "passive"))
      (node (ref "ETHERNET_IC") (pin "2") (pinfunction "OSC2_2") (pintype "output"))
      (node (ref "U$5") (pin "1") (pinfunction "1_1") (pintype "bidirectional"))
    )
    (net (code "28") (name "OSC_IN") (class "Default")
      (node (ref "C1") (pin "1") (pinfunction "1_1") (pintype "passive"))
      (node (ref "U$3") (pin "12") (pinfunction "PF0/OSC-IN_12") (pintype "bidirectional"))
      (node (ref "Y1") (pin "P$2") (pinfunction "2_P$2") (pintype "passive"))
    )
    (net (code "29") (name "OSC_OUT") (class "Default")
      (node (ref "C2") (pin "1") (pinfunction "1_1") (pintype "passive"))
      (node (ref "U$3") (pin "13") (pinfunction "PF1/OSC-OUT_13") (pintype "bidirectional"))
      (node (ref "Y1") (pin "P$1") (pinfunction "1_P$1") (pintype "passive"))
    )
    (net (code "30") (name "PEAK_RESET") (class "Default")
      (node (ref "U$3") (pin "87") (pinfunction "PD6_87") (pintype "input"))
      (node (ref "U2") (pin "D23") (pinfunction "D23/A9_D23") (pintype "bidirectional"))
    )
    (net (code "31") (name "RCT") (class "Default")
      (node (ref "C30") (pin "1") (pinfunction "1_1") (pintype "passive"))
      (node (ref "P1") (pin "5") (pinfunction "RCT_5") (pintype "passive"))
      (node (ref "R15") (pin "1") (pinfunction "1_1") (pintype "passive"))
      (node (ref "R16") (pin "2") (pinfunction "2_2") (pintype "passive"))
    )
    (net (code "32") (name "RD_N") (class "Default")
      (node (ref "C32") (pin "1") (pinfunction "1_1") (pintype "passive"))
      (node (ref "P1") (pin "6") (pinfunction "RD-_6") (pintype "passive"))
    )
    (net (code "33") (name "RD_P") (class "Default")
      (node (ref "C31") (pin "2") (pinfunction "2_2") (pintype "passive"))
      (node (ref "P1") (pin "4") (pinfunction "RD+_4") (pintype "passive"))
    )
    (net (code "34") (name "SCL") (class "Default")
      (node (ref "R4") (pin "1") (pinfunction "1_1") (pintype "passive"))
      (node (ref "U$3") (pin "68") (pinfunction "PA9_68") (pintype "bidirectional"))
      (node (ref "U2") (pin "D19") (pinfunction "D19/A5_D19") (pintype "bidirectional"))
    )
    (net (code "35") (name "SDA") (class "Default")
      (node (ref "R5") (pin "1") (pinfunction "1_1") (pintype "passive"))
      (node (ref "U$3") (pin "69") (pinfunction "PA10_69") (pintype "bidirectional"))
      (node (ref "U2") (pin "D18") (pinfunction "D18/A4_D18") (pintype "bidirectional"))
    )
    (net (code "36") (name "SPI4_MISO") (class "Default")
      (node (ref "ETHERNET_IC") (pin "36") (pinfunction "SI/RD/R~{W}_36") (pintype "input"))
      (node (ref "U$3") (pin "44") (pinfunction "PE13_44") (pintype "input"))
    )
    (net (code "37") (name "SPI4_MOSI") (class "Default")
      (node (ref "ETHERNET_IC") (pin "35") (pinfunction "SO/WR/EN_35") (pintype "bidirectional"))
      (node (ref "U$3") (pin "45") (pinfunction "PE14_45") (pintype "input"))
    )
    (net (code "38") (name "SPI4_NSS") (class "Default")
      (node (ref "ETHERNET_IC") (pin "34") (pinfunction "~{CS/CS}_34") (pintype "input"))
      (node (ref "U$3") (pin "42") (pinfunction "PE11_42") (pintype "input"))
    )
    (net (code "39") (name "SPI4_SCK") (class "Default")
      (node (ref "ETHERNET_IC") (pin "37") (pinfunction "SCK/AL_37") (pintype "input"))
      (node (ref "U$3") (pin "43") (pinfunction "PE12_43") (pintype "input"))
    )
    (net (code "40") (name "SWCLK") (class "Default")
      (node (ref "JP1") (pin "4") (pinfunction "SWCLK/TCK_4") (pintype "bidirectional"))
      (node (ref "U$3") (pin "76") (pinfunction "PA14_76") (pintype "bidirectional"))
    )
    (net (code "41") (name "SWDIO") (class "Default")
      (node (ref "JP1") (pin "2") (pinfunction "SWDIO/TMS_2") (pintype "bidirectional"))
      (node (ref "U$3") (pin "72") (pinfunction "PA13_72") (pintype "bidirectional"))
    )
    (net (code "42") (name "TCT") (class "Default")
      (node (ref "C29") (pin "1") (pinfunction "1_1") (pintype "passive"))
      (node (ref "P1") (pin "2") (pinfunction "TCT_2") (pintype "passive"))
      (node (ref "R14") (pin "1") (pinfunction "1_1") (pintype "passive"))
    )
    (net (code "43") (name "TPIN_N") (class "Default")
      (node (ref "C32") (pin "2") (pinfunction "2_2") (pintype "passive"))
      (node (ref "ETHERNET_IC") (pin "17") (pinfunction "TPIN-_17") (pintype "input"))
      (node (ref "R16") (pin "1") (pinfunction "1_1") (pintype "passive"))
    )
    (net (code "44") (name "TPIN_P") (class "Default")
      (node (ref "C31") (pin "1") (pinfunction "1_1") (pintype "passive"))
      (node (ref "ETHERNET_IC") (pin "16") (pinfunction "TPIN+_16") (pintype "input"))
      (node (ref "R15") (pin "2") (pinfunction "2_2") (pintype "passive"))
    )
    (net (code "45") (name "TPOUT_N") (class "Default")
      (node (ref "ETHERNET_IC") (pin "21") (pinfunction "TPOUT-_21") (pintype "output"))
      (node (ref "P1") (pin "3") (pinfunction "TD-_3") (pintype "passive"))
      (node (ref "R13") (pin "1") (pinfunction "1_1") (pintype "passive"))
    )
    (net (code "46") (name "TPOUT_P") (class "Default")
      (node (ref "ETHERNET_IC") (pin "20") (pinfunction "TPOUT+_20") (pintype "output"))
      (node (ref "P1") (pin "1") (pinfunction "TD+_1") (pintype "passive"))
      (node (ref "R12") (pin "2") (pinfunction "2_2") (pintype "passive"))
    )
    (net (code "47") (name "TRACESWO") (class "Default")
      (node (ref "JP1") (pin "6") (pinfunction "SWO/TDO_6") (pintype "bidirectional"))
      (node (ref "U$3") (pin "89") (pinfunction "PB3_89") (pintype "bidirectional"))
    )
    (net (code "48") (name "UART1_RX") (class "Default")
      (node (ref "U$3") (pin "93") (pinfunction "PB7_93") (pintype "bidirectional"))
    )
    (net (code "49") (name "UART1_TX") (class "Default")
      (node (ref "U$3") (pin "92") (pinfunction "PB6_92") (pintype "bidirectional"))
    )
    (net (code "50") (name "UART3_RX") (class "Default")
      (node (ref "U$3") (pin "56") (pinfunction "PD9_56") (pintype "input"))
      (node (ref "U2") (pin "D0") (pinfunction "D0/RX1_D0") (pintype "bidirectional"))
    )
    (net (code "51") (name "UART3_TX") (class "Default")
      (node (ref "U$3") (pin "55") (pinfunction "PD8_55") (pintype "input"))
      (node (ref "U2") (pin "D1") (pinfunction "D1/TX1_D1") (pintype "bidirectional"))
    )
    (net (code "52") (name "USB_D+") (class "Default")
      (node (ref "R3") (pin "2") (pinfunction "2_2") (pintype "passive"))
      (node (ref "T2") (pin "1") (pinfunction "S_1") (pintype "passive"))
      (node (ref "U$4") (pin "3") (pinfunction "D+_3") (pintype "bidirectional"))
    )
    (net (code "53") (name "USB_D-") (class "Default")
      (node (ref "R2") (pin "2") (pinfunction "2_2") (pintype "passive"))
      (node (ref "U$4") (pin "2") (pinfunction "D-_2") (pintype "bidirectional"))
    )
    (net (code "54") (name "USB_D_N") (class "Default")
      (node (ref "R2") (pin "1") (pinfunction "1_1") (pintype "passive"))
      (node (ref "U$3") (pin "70") (pinfunction "PA11_70") (pintype "bidirectional"))
    )
    (net (code "55") (name "USB_D_P") (class "Default")
      (node (ref "R3") (pin "1") (pinfunction "1_1") (pintype "passive"))
      (node (ref "U$3") (pin "71") (pinfunction "PA12_71") (pintype "bidirectional"))
    )
    (net (code "56") (name "VCAP") (class "Default")
      (node (ref "C28") (pin "1") (pinfunction "1_1") (pintype "passive"))
      (node (ref "ETHERNET_IC") (pin "43") (pinfunction "VCAP_43") (pintype "power_in"))
    )
    (net (code "57") (name "VCC") (class "Default")
      (node (ref "C19") (pin "1") (pinfunction "1_1") (pintype "passive"))
      (node (ref "C24") (pin "1") (pinfunction "1_1") (pintype "passive"))
      (node (ref "U$2") (pin "3") (pinfunction "VDD_3") (pintype "bidirectional"))
      (node (ref "U1") (pin "1") (pinfunction "VIN_1") (pintype "bidirectional"))
      (node (ref "U1") (pin "3") (pinfunction "EN_3") (pintype "bidirectional"))
      (node (ref "U2") (pin "VIN") (pinfunction "VIN_VIN") (pintype "power_in"))
    )
    (net (code "58") (name "VUSB") (class "Default")
      (node (ref "U2") (pin "VUSB") (pinfunction "VUSB_VUSB") (pintype "power_in"))
    )
    (net (code "59") (name "unconnected-(CON1-+5V-Pad1)") (class "Default")
      (node (ref "CON1") (pin "1") (pinfunction "+5V_1") (pintype "bidirectional"))
    )
    (net (code "60") (name "unconnected-(CON2-+5V-Pad1)") (class "Default")
      (node (ref "CON2") (pin "1") (pinfunction "+5V_1") (pintype "bidirectional"))
    )
    (net (code "61") (name "unconnected-(ETHERNET_IC-AD0-Pad38)") (class "Default")
      (node (ref "ETHERNET_IC") (pin "38") (pinfunction "AD0_38") (pintype "bidirectional"))
    )
    (net (code "62") (name "unconnected-(ETHERNET_IC-AD1-Pad39)") (class "Default")
      (node (ref "ETHERNET_IC") (pin "39") (pinfunction "AD1_39") (pintype "bidirectional"))
    )
    (net (code "63") (name "unconnected-(ETHERNET_IC-AD2-Pad40)") (class "Default")
      (node (ref "ETHERNET_IC") (pin "40") (pinfunction "AD2_40") (pintype "bidirectional"))
    )
    (net (code "64") (name "unconnected-(ETHERNET_IC-AD3-Pad41)") (class "Default")
      (node (ref "ETHERNET_IC") (pin "41") (pinfunction "AD3_41") (pintype "bidirectional"))
    )
    (net (code "65") (name "unconnected-(ETHERNET_IC-AD4-Pad5)") (class "Default")
      (node (ref "ETHERNET_IC") (pin "5") (pinfunction "AD4_5") (pintype "bidirectional"))
    )
    (net (code "66") (name "unconnected-(ETHERNET_IC-AD5-Pad6)") (class "Default")
      (node (ref "ETHERNET_IC") (pin "6") (pinfunction "AD5_6") (pintype "bidirectional"))
    )
    (net (code "67") (name "unconnected-(ETHERNET_IC-AD6-Pad7)") (class "Default")
      (node (ref "ETHERNET_IC") (pin "7") (pinfunction "AD6_7") (pintype "bidirectional"))
    )
    (net (code "68") (name "unconnected-(ETHERNET_IC-AD7-Pad8)") (class "Default")
      (node (ref "ETHERNET_IC") (pin "8") (pinfunction "AD7_8") (pintype "bidirectional"))
    )
    (net (code "69") (name "unconnected-(ETHERNET_IC-AD8-Pad25)") (class "Default")
      (node (ref "ETHERNET_IC") (pin "25") (pinfunction "AD8_25") (pintype "bidirectional"))
    )
    (net (code "70") (name "unconnected-(ETHERNET_IC-AD9-Pad26)") (class "Default")
      (node (ref "ETHERNET_IC") (pin "26") (pinfunction "AD9_26") (pintype "bidirectional"))
    )
    (net (code "71") (name "unconnected-(ETHERNET_IC-AD10-Pad27)") (class "Default")
      (node (ref "ETHERNET_IC") (pin "27") (pinfunction "AD10_27") (pintype "bidirectional"))
    )
    (net (code "72") (name "unconnected-(ETHERNET_IC-AD11-Pad28)") (class "Default")
      (node (ref "ETHERNET_IC") (pin "28") (pinfunction "AD11_28") (pintype "bidirectional"))
    )
    (net (code "73") (name "unconnected-(ETHERNET_IC-AD12-Pad29)") (class "Default")
      (node (ref "ETHERNET_IC") (pin "29") (pinfunction "AD12_29") (pintype "bidirectional"))
    )
    (net (code "74") (name "unconnected-(ETHERNET_IC-AD13-Pad30)") (class "Default")
      (node (ref "ETHERNET_IC") (pin "30") (pinfunction "AD13_30") (pintype "bidirectional"))
    )
    (net (code "75") (name "unconnected-(ETHERNET_IC-AD14-Pad31)") (class "Default")
      (node (ref "ETHERNET_IC") (pin "31") (pinfunction "AD14_31") (pintype "bidirectional"))
    )
    (net (code "76") (name "unconnected-(ETHERNET_IC-CLKOUT-Pad23)") (class "Default")
      (node (ref "ETHERNET_IC") (pin "23") (pinfunction "CLKOUT_23") (pintype "output"))
    )
    (net (code "77") (name "unconnected-(ETHERNET_IC-PSPCFG0-Pad32)") (class "Default")
      (node (ref "ETHERNET_IC") (pin "32") (pinfunction "PSPCFG0_32") (pintype "output"))
    )
    (net (code "78") (name "unconnected-(JP1-NC{slash}TDI-Pad8)") (class "Default")
      (node (ref "JP1") (pin "8") (pinfunction "NC/TDI_8") (pintype "bidirectional"))
    )
    (net (code "79") (name "unconnected-(P1-CH_GND-Pad13)") (class "Default")
      (node (ref "P1") (pin "13") (pinfunction "CH_GND_13") (pintype "passive"))
    )
    (net (code "80") (name "unconnected-(P1-CH_GND-Pad14)") (class "Default")
      (node (ref "P1") (pin "14") (pinfunction "CH_GND_14") (pintype "passive"))
    )
    (net (code "81") (name "unconnected-(U$3A-PA1-Pad24)") (class "Default")
      (node (ref "U$3") (pin "24") (pinfunction "PA1_24") (pintype "bidirectional"))
    )
    (net (code "82") (name "unconnected-(U$3A-PA2-Pad25)") (class "Default")
      (node (ref "U$3") (pin "25") (pinfunction "PA2_25") (pintype "bidirectional"))
    )
    (net (code "83") (name "unconnected-(U$3A-PA3-Pad26)") (class "Default")
      (node (ref "U$3") (pin "26") (pinfunction "PA3_26") (pintype "bidirectional"))
    )
    (net (code "84") (name "unconnected-(U$3A-PA5-Pad30)") (class "Default")
      (node (ref "U$3") (pin "30") (pinfunction "PA5_30") (pintype "bidirectional"))
    )
    (net (code "85") (name "unconnected-(U$3A-PA6-Pad31)") (class "Default")
      (node (ref "U$3") (pin "31") (pinfunction "PA6_31") (pintype "bidirectional"))
    )
    (net (code "86") (name "unconnected-(U$3A-PA7-Pad32)") (class "Default")
      (node (ref "U$3") (pin "32") (pinfunction "PA7_32") (pintype "bidirectional"))
    )
    (net (code "87") (name "unconnected-(U$3A-PA8-Pad67)") (class "Default")
      (node (ref "U$3") (pin "67") (pinfunction "PA8_67") (pintype "bidirectional"))
    )
    (net (code "88") (name "unconnected-(U$3A-PA15-Pad77)") (class "Default")
      (node (ref "U$3") (pin "77") (pinfunction "PA15_77") (pintype "bidirectional"))
    )
    (net (code "89") (name "unconnected-(U$3B-PB0-Pad35)") (class "Default")
      (node (ref "U$3") (pin "35") (pinfunction "PB0_35") (pintype "bidirectional"))
    )
    (net (code "90") (name "unconnected-(U$3B-PB1-Pad36)") (class "Default")
      (node (ref "U$3") (pin "36") (pinfunction "PB1_36") (pintype "bidirectional"))
    )
    (net (code "91") (name "unconnected-(U$3B-PB2-Pad37)") (class "Default")
      (node (ref "U$3") (pin "37") (pinfunction "PB2_37") (pintype "bidirectional"))
    )
    (net (code "92") (name "unconnected-(U$3B-PB4-Pad90)") (class "Default")
      (node (ref "U$3") (pin "90") (pinfunction "PB4_90") (pintype "bidirectional"))
    )
    (net (code "93") (name "unconnected-(U$3B-PB5-Pad91)") (class "Default")
      (node (ref "U$3") (pin "91") (pinfunction "PB5_91") (pintype "bidirectional"))
    )
    (net (code "94") (name "unconnected-(U$3B-PB10-Pad47)") (class "Default")
      (node (ref "U$3") (pin "47") (pinfunction "PB10_47") (pintype "bidirectional"))
    )
    (net (code "95") (name "unconnected-(U$3B-PB11-Pad48)") (class "Default")
      (node (ref "U$3") (pin "48") (pinfunction "PB11_48") (pintype "bidirectional"))
    )
    (net (code "96") (name "unconnected-(U$3B-PB12-Pad51)") (class "Default")
      (node (ref "U$3") (pin "51") (pinfunction "PB12_51") (pintype "bidirectional"))
    )
    (net (code "97") (name "unconnected-(U$3B-PB15-Pad54)") (class "Default")
      (node (ref "U$3") (pin "54") (pinfunction "PB15_54") (pintype "bidirectional"))
    )
    (net (code "98") (name "unconnected-(U$3D-PD7-Pad88)") (class "Default")
      (node (ref "U$3") (pin "88") (pinfunction "PD7_88") (pintype "input"))
    )
    (net (code "99") (name "unconnected-(U$3D-PD10-Pad57)") (class "Default")
      (node (ref "U$3") (pin "57") (pinfunction "PD10_57") (pintype "input"))
    )
    (net (code "100") (name "unconnected-(U$3D-PD11-Pad58)") (class "Default")
      (node (ref "U$3") (pin "58") (pinfunction "PD11_58") (pintype "input"))
    )
    (net (code "101") (name "unconnected-(U$3D-PD12-Pad59)") (class "Default")
      (node (ref "U$3") (pin "59") (pinfunction "PD12_59") (pintype "input"))
    )
    (net (code "102") (name "unconnected-(U$3D-PD13-Pad60)") (class "Default")
      (node (ref "U$3") (pin "60") (pinfunction "PD13_60") (pintype "input"))
    )
    (net (code "103") (name "unconnected-(U$3D-PD14-Pad61)") (class "Default")
      (node (ref "U$3") (pin "61") (pinfunction "PD14_61") (pintype "input"))
    )
    (net (code "104") (name "unconnected-(U$3D-PD15-Pad62)") (class "Default")
      (node (ref "U$3") (pin "62") (pinfunction "PD15_62") (pintype "input"))
    )
    (net (code "105") (name "unconnected-(U$3F-PC14{slash}OSC32-IN-Pad8)") (class "Default")
      (node (ref "U$3") (pin "8") (pinfunction "PC14/OSC32-IN_8") (pintype "bidirectional"))
    )
    (net (code "106") (name "unconnected-(U$3F-PC15{slash}OSC32-OUT-Pad9)") (class "Default")
      (node (ref "U$3") (pin "9") (pinfunction "PC15/OSC32-OUT_9") (pintype "bidirectional"))
    )
    (net (code "107") (name "unconnected-(U$3F-VBAT-Pad6)") (class "Default")
      (node (ref "U$3") (pin "6") (pinfunction "VBAT_6") (pintype "bidirectional"))
    )
    (net (code "108") (name "unconnected-(U$3G-PE0-Pad97)") (class "Default")
      (node (ref "U$3") (pin "97") (pinfunction "PE0_97") (pintype "input"))
    )
    (net (code "109") (name "unconnected-(U$3G-PE1-Pad98)") (class "Default")
      (node (ref "U$3") (pin "98") (pinfunction "PE1_98") (pintype "input"))
    )
    (net (code "110") (name "unconnected-(U$3G-PE2-Pad1)") (class "Default")
      (node (ref "U$3") (pin "1") (pinfunction "PE2_1") (pintype "input"))
    )
    (net (code "111") (name "unconnected-(U$3G-PE3-Pad2)") (class "Default")
      (node (ref "U$3") (pin "2") (pinfunction "PE3_2") (pintype "input"))
    )
    (net (code "112") (name "unconnected-(U$3G-PE4-Pad3)") (class "Default")
      (node (ref "U$3") (pin "3") (pinfunction "PE4_3") (pintype "input"))
    )
    (net (code "113") (name "unconnected-(U$3G-PE5-Pad4)") (class "Default")
      (node (ref "U$3") (pin "4") (pinfunction "PE5_4") (pintype "input"))
    )
    (net (code "114") (name "unconnected-(U$3G-PE6-Pad5)") (class "Default")
      (node (ref "U$3") (pin "5") (pinfunction "PE6_5") (pintype "input"))
    )
    (net (code "115") (name "unconnected-(U$3G-PE7-Pad38)") (class "Default")
      (node (ref "U$3") (pin "38") (pinfunction "PE7_38") (pintype "input"))
    )
    (net (code "116") (name "unconnected-(U$3G-PE8-Pad39)") (class "Default")
      (node (ref "U$3") (pin "39") (pinfunction "PE8_39") (pintype "input"))
    )
    (net (code "117") (name "unconnected-(U$3G-PE9-Pad40)") (class "Default")
      (node (ref "U$3") (pin "40") (pinfunction "PE9_40") (pintype "input"))
    )
    (net (code "118") (name "unconnected-(U$3G-PE10-Pad41)") (class "Default")
      (node (ref "U$3") (pin "41") (pinfunction "PE10_41") (pintype "input"))
    )
    (net (code "119") (name "unconnected-(U$3G-PE15-Pad46)") (class "Default")
      (node (ref "U$3") (pin "46") (pinfunction "PE15_46") (pintype "input"))
    )
    (net (code "120") (name "unconnected-(U$4-ID-Pad4)") (class "Default")
      (node (ref "U$4") (pin "4") (pinfunction "ID_4") (pintype "bidirectional"))
    )
    (net (code "121") (name "unconnected-(U1-NC-Pad4)") (class "Default")
      (node (ref "U1") (pin "4") (pinfunction "NC_4") (pintype "bidirectional"))
    )
    (net (code "122") (name "unconnected-(U2-D3{slash}CANTX-PadD3)") (class "Default")
      (node (ref "U2") (pin "D3") (pinfunction "D3/CANTX_D3") (pintype "bidirectional"))
    )
    (net (code "123") (name "unconnected-(U2-D4{slash}CANRX-PadD4)") (class "Default")
      (node (ref "U2") (pin "D4") (pinfunction "D4/CANRX_D4") (pintype "bidirectional"))
    )
    (net (code "124") (name "unconnected-(U2-D5{slash}TX1-PadD5)") (class "Default")
      (node (ref "U2") (pin "D5") (pinfunction "D5/TX1_D5") (pintype "bidirectional"))
    )
    (net (code "125") (name "unconnected-(U2-D7{slash}RX3-PadD7)") (class "Default")
      (node (ref "U2") (pin "D7") (pinfunction "D7/RX3_D7") (pintype "bidirectional"))
    )
    (net (code "126") (name "unconnected-(U2-D13{slash}LED-PadD13)") (class "Default")
      (node (ref "U2") (pin "D13") (pinfunction "D13/LED_D13") (pintype "bidirectional"))
    )
    (net (code "127") (name "unconnected-(U2-D14{slash}A0-PadD14)") (class "Default")
      (node (ref "U2") (pin "D14") (pinfunction "D14/A0_D14") (pintype "bidirectional"))
    )
    (net (code "128") (name "unconnected-(U2-D15{slash}A1-PadD15)") (class "Default")
      (node (ref "U2") (pin "D15") (pinfunction "D15/A1_D15") (pintype "bidirectional"))
    )
    (net (code "129") (name "unconnected-(U2-D16{slash}A2-PadD16)") (class "Default")
      (node (ref "U2") (pin "D16") (pinfunction "D16/A2_D16") (pintype "bidirectional"))
    )
    (net (code "130") (name "unconnected-(U2-D17{slash}A3-PadD17)") (class "Default")
      (node (ref "U2") (pin "D17") (pinfunction "D17/A3_D17") (pintype "bidirectional"))
    )
    (net (code "131") (name "unconnected-(U2-D20{slash}A6-PadD20)") (class "Default")
      (node (ref "U2") (pin "D20") (pinfunction "D20/A6_D20") (pintype "bidirectional"))
    )
    (net (code "132") (name "unconnected-(U2-D21{slash}A7-PadD21)") (class "Default")
      (node (ref "U2") (pin "D21") (pinfunction "D21/A7_D21") (pintype "bidirectional"))
    )
    (net (code "133") (name "unconnected-(U2-D22{slash}A8-PadD22)") (class "Default")
      (node (ref "U2") (pin "D22") (pinfunction "D22/A8_D22") (pintype "bidirectional"))
    )
    (net (code "134") (name "unconnected-(U2-PadA10)") (class "Default")
      (node (ref "U2") (pin "A10") (pinfunction "A10_A10") (pintype "bidirectional"))
    )
    (net (code "135") (name "unconnected-(U2-PadA11)") (class "Default")
      (node (ref "U2") (pin "A11") (pinfunction "A11_A11") (pintype "bidirectional"))
    )
    (net (code "136") (name "unconnected-(U2-PadD2)") (class "Default")
      (node (ref "U2") (pin "D2") (pinfunction "D2_D2") (pintype "bidirectional"))
    )
    (net (code "137") (name "unconnected-(U2-PadD6)") (class "Default")
      (node (ref "U2") (pin "D6") (pinfunction "D6_D6") (pintype "bidirectional"))
    )
    (net (code "138") (name "unconnected-(U2-PadPROGRAM)") (class "Default")
      (node (ref "U2") (pin "PROGRAM") (pinfunction "PROGRAM_PROGRAM") (pintype "input"))
    )
    (net (code "139") (name "unconnected-(U2-PadVBAT)") (class "Default")
      (node (ref "U2") (pin "VBAT") (pinfunction "VBAT_VBAT") (pintype "input"))
    )
    (net (code "140") (name "~{INT{slash}SPISEL}") (class "Default")
      (node (ref "ETHERNET_IC") (pin "24") (pinfunction "~{INT/SPISEL}_24") (pintype "input"))
      (node (ref "R11") (pin "2") (pinfunction "2_2") (pintype "passive"))
    )
    (net (code "141") (name "~{RST}") (class "Default")
      (node (ref "JP1") (pin "10") (pinfunction "~{RESET}_10") (pintype "bidirectional"))
      (node (ref "R1") (pin "1") (pinfunction "1_1") (pintype "passive"))
      (node (ref "S1") (pin "3") (pinfunction "2_3") (pintype "passive"))
      (node (ref "S1") (pin "4") (pinfunction "2_4") (pintype "passive"))
      (node (ref "U$3") (pin "14") (pinfunction "NRST_14") (pintype "bidirectional"))
    )
  )
)
